# con-bot-j1-0.net
KiCad netlist of a schematic drawn in Altium Designer
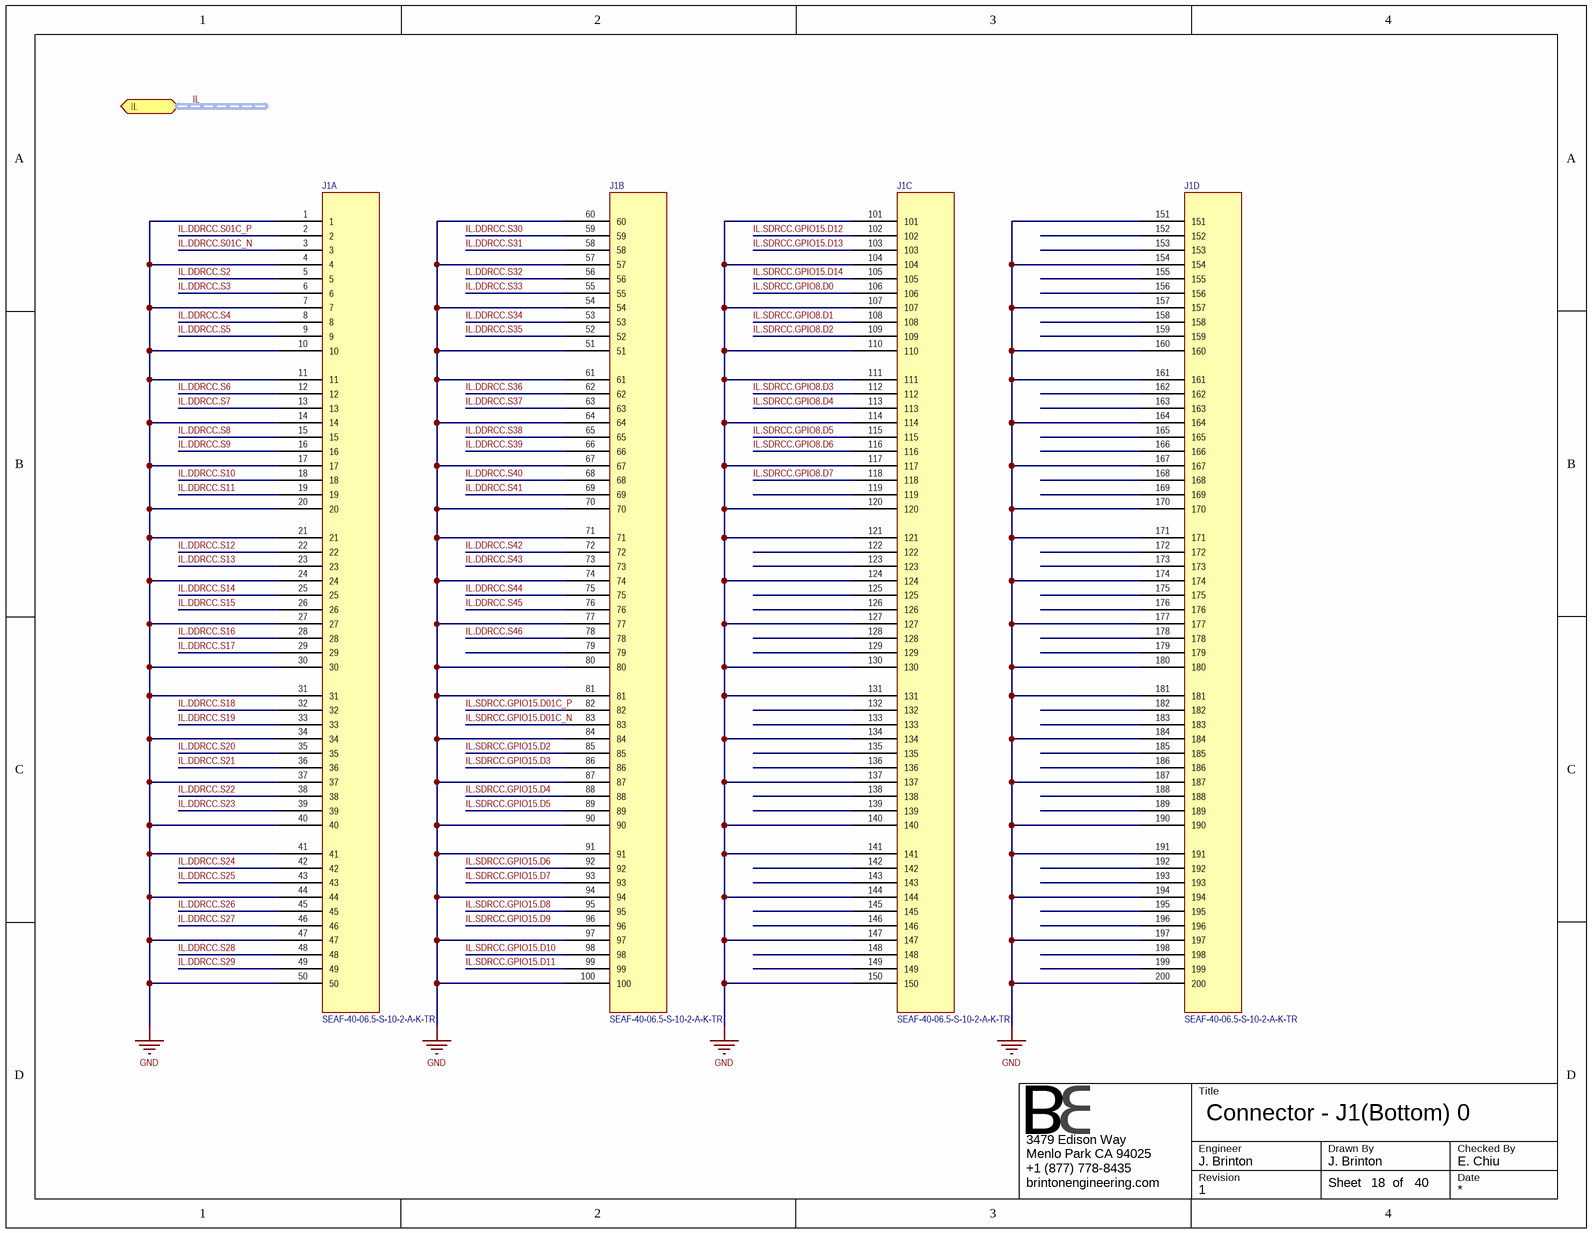
[diagram p0: con-bot-j1-0.SchDoc]

(export (version "E")
  (design (tool "Eeschema 10.0.6"))
  (components
    (comp (ref "J1")
      (value "SEAF-40-06.5-S-10-2-A-K-TR")
      (footprint "samtec:SEAF-40-06.5-S-10-2-A-K-TR")
      (description "Terminal Array Assembly, Surface Mount, 0.050\" Pitch, 400 Pins")
      (fields (field (name "MANUFACTURER") "Samtec"))
      (libsource (lib "samtec") (part "SEAF-40-06.5-S-10-2-A-K-TR"))
    )
  )
  (nets
    (net (code "2") (name "/IL.DDRCC.S01C_N") (class "Default")
      (node (ref "J1") (pin "3") (pinfunction "3_3") (pintype "passive"))
    )
    (net (code "3") (name "/IL.DDRCC.S01C_P") (class "Default")
      (node (ref "J1") (pin "2") (pinfunction "2_2") (pintype "passive"))
    )
    (net (code "4") (name "/IL.DDRCC.S2") (class "Default")
      (node (ref "J1") (pin "5") (pinfunction "5_5") (pintype "passive"))
    )
    (net (code "5") (name "/IL.DDRCC.S3") (class "Default")
      (node (ref "J1") (pin "6") (pinfunction "6_6") (pintype "passive"))
    )
    (net (code "6") (name "/IL.DDRCC.S4") (class "Default")
      (node (ref "J1") (pin "8") (pinfunction "8_8") (pintype "passive"))
    )
    (net (code "7") (name "/IL.DDRCC.S5") (class "Default")
      (node (ref "J1") (pin "9") (pinfunction "9_9") (pintype "passive"))
    )
    (net (code "8") (name "/IL.DDRCC.S6") (class "Default")
      (node (ref "J1") (pin "12") (pinfunction "12_12") (pintype "passive"))
    )
    (net (code "9") (name "/IL.DDRCC.S7") (class "Default")
      (node (ref "J1") (pin "13") (pinfunction "13_13") (pintype "passive"))
    )
    (net (code "10") (name "/IL.DDRCC.S8") (class "Default")
      (node (ref "J1") (pin "15") (pinfunction "15_15") (pintype "passive"))
    )
    (net (code "11") (name "/IL.DDRCC.S9") (class "Default")
      (node (ref "J1") (pin "16") (pinfunction "16_16") (pintype "passive"))
    )
    (net (code "12") (name "/IL.DDRCC.S10") (class "Default")
      (node (ref "J1") (pin "18") (pinfunction "18_18") (pintype "passive"))
    )
    (net (code "13") (name "/IL.DDRCC.S11") (class "Default")
      (node (ref "J1") (pin "19") (pinfunction "19_19") (pintype "passive"))
    )
    (net (code "14") (name "/IL.DDRCC.S12") (class "Default")
      (node (ref "J1") (pin "22") (pinfunction "22_22") (pintype "passive"))
    )
    (net (code "15") (name "/IL.DDRCC.S13") (class "Default")
      (node (ref "J1") (pin "23") (pinfunction "23_23") (pintype "passive"))
    )
    (net (code "16") (name "/IL.DDRCC.S14") (class "Default")
      (node (ref "J1") (pin "25") (pinfunction "25_25") (pintype "passive"))
    )
    (net (code "17") (name "/IL.DDRCC.S15") (class "Default")
      (node (ref "J1") (pin "26") (pinfunction "26_26") (pintype "passive"))
    )
    (net (code "18") (name "/IL.DDRCC.S16") (class "Default")
      (node (ref "J1") (pin "28") (pinfunction "28_28") (pintype "passive"))
    )
    (net (code "19") (name "/IL.DDRCC.S17") (class "Default")
      (node (ref "J1") (pin "29") (pinfunction "29_29") (pintype "passive"))
    )
    (net (code "20") (name "/IL.DDRCC.S18") (class "Default")
      (node (ref "J1") (pin "32") (pinfunction "32_32") (pintype "passive"))
    )
    (net (code "21") (name "/IL.DDRCC.S19") (class "Default")
      (node (ref "J1") (pin "33") (pinfunction "33_33") (pintype "passive"))
    )
    (net (code "22") (name "/IL.DDRCC.S20") (class "Default")
      (node (ref "J1") (pin "35") (pinfunction "35_35") (pintype "passive"))
    )
    (net (code "23") (name "/IL.DDRCC.S21") (class "Default")
      (node (ref "J1") (pin "36") (pinfunction "36_36") (pintype "passive"))
    )
    (net (code "24") (name "/IL.DDRCC.S22") (class "Default")
      (node (ref "J1") (pin "38") (pinfunction "38_38") (pintype "passive"))
    )
    (net (code "25") (name "/IL.DDRCC.S23") (class "Default")
      (node (ref "J1") (pin "39") (pinfunction "39_39") (pintype "passive"))
    )
    (net (code "26") (name "/IL.DDRCC.S24") (class "Default")
      (node (ref "J1") (pin "42") (pinfunction "42_42") (pintype "passive"))
    )
    (net (code "27") (name "/IL.DDRCC.S25") (class "Default")
      (node (ref "J1") (pin "43") (pinfunction "43_43") (pintype "passive"))
    )
    (net (code "28") (name "/IL.DDRCC.S26") (class "Default")
      (node (ref "J1") (pin "45") (pinfunction "45_45") (pintype "passive"))
    )
    (net (code "29") (name "/IL.DDRCC.S27") (class "Default")
      (node (ref "J1") (pin "46") (pinfunction "46_46") (pintype "passive"))
    )
    (net (code "30") (name "/IL.DDRCC.S28") (class "Default")
      (node (ref "J1") (pin "48") (pinfunction "48_48") (pintype "passive"))
    )
    (net (code "31") (name "/IL.DDRCC.S29") (class "Default")
      (node (ref "J1") (pin "49") (pinfunction "49_49") (pintype "passive"))
    )
    (net (code "32") (name "/IL.DDRCC.S30") (class "Default")
      (node (ref "J1") (pin "59") (pinfunction "59_59") (pintype "passive"))
    )
    (net (code "33") (name "/IL.DDRCC.S31") (class "Default")
      (node (ref "J1") (pin "58") (pinfunction "58_58") (pintype "passive"))
    )
    (net (code "34") (name "/IL.DDRCC.S32") (class "Default")
      (node (ref "J1") (pin "56") (pinfunction "56_56") (pintype "passive"))
    )
    (net (code "35") (name "/IL.DDRCC.S33") (class "Default")
      (node (ref "J1") (pin "55") (pinfunction "55_55") (pintype "passive"))
    )
    (net (code "36") (name "/IL.DDRCC.S34") (class "Default")
      (node (ref "J1") (pin "53") (pinfunction "53_53") (pintype "passive"))
    )
    (net (code "37") (name "/IL.DDRCC.S35") (class "Default")
      (node (ref "J1") (pin "52") (pinfunction "52_52") (pintype "passive"))
    )
    (net (code "38") (name "/IL.DDRCC.S36") (class "Default")
      (node (ref "J1") (pin "62") (pinfunction "62_62") (pintype "passive"))
    )
    (net (code "39") (name "/IL.DDRCC.S37") (class "Default")
      (node (ref "J1") (pin "63") (pinfunction "63_63") (pintype "passive"))
    )
    (net (code "40") (name "/IL.DDRCC.S38") (class "Default")
      (node (ref "J1") (pin "65") (pinfunction "65_65") (pintype "passive"))
    )
    (net (code "41") (name "/IL.DDRCC.S39") (class "Default")
      (node (ref "J1") (pin "66") (pinfunction "66_66") (pintype "passive"))
    )
    (net (code "42") (name "/IL.DDRCC.S40") (class "Default")
      (node (ref "J1") (pin "68") (pinfunction "68_68") (pintype "passive"))
    )
    (net (code "43") (name "/IL.DDRCC.S41") (class "Default")
      (node (ref "J1") (pin "69") (pinfunction "69_69") (pintype "passive"))
    )
    (net (code "44") (name "/IL.DDRCC.S42") (class "Default")
      (node (ref "J1") (pin "72") (pinfunction "72_72") (pintype "passive"))
    )
    (net (code "45") (name "/IL.DDRCC.S43") (class "Default")
      (node (ref "J1") (pin "73") (pinfunction "73_73") (pintype "passive"))
    )
    (net (code "46") (name "/IL.DDRCC.S44") (class "Default")
      (node (ref "J1") (pin "75") (pinfunction "75_75") (pintype "passive"))
    )
    (net (code "47") (name "/IL.DDRCC.S45") (class "Default")
      (node (ref "J1") (pin "76") (pinfunction "76_76") (pintype "passive"))
    )
    (net (code "48") (name "/IL.DDRCC.S46") (class "Default")
      (node (ref "J1") (pin "78") (pinfunction "78_78") (pintype "passive"))
    )
    (net (code "49") (name "/IL.SDRCC.GPIO8.D0") (class "Default")
      (node (ref "J1") (pin "106") (pinfunction "106_106") (pintype "passive"))
    )
    (net (code "50") (name "/IL.SDRCC.GPIO8.D1") (class "Default")
      (node (ref "J1") (pin "108") (pinfunction "108_108") (pintype "passive"))
    )
    (net (code "51") (name "/IL.SDRCC.GPIO8.D2") (class "Default")
      (node (ref "J1") (pin "109") (pinfunction "109_109") (pintype "passive"))
    )
    (net (code "52") (name "/IL.SDRCC.GPIO8.D3") (class "Default")
      (node (ref "J1") (pin "112") (pinfunction "112_112") (pintype "passive"))
    )
    (net (code "53") (name "/IL.SDRCC.GPIO8.D4") (class "Default")
      (node (ref "J1") (pin "113") (pinfunction "113_113") (pintype "passive"))
    )
    (net (code "54") (name "/IL.SDRCC.GPIO8.D5") (class "Default")
      (node (ref "J1") (pin "115") (pinfunction "115_115") (pintype "passive"))
    )
    (net (code "55") (name "/IL.SDRCC.GPIO8.D6") (class "Default")
      (node (ref "J1") (pin "116") (pinfunction "116_116") (pintype "passive"))
    )
    (net (code "56") (name "/IL.SDRCC.GPIO8.D7") (class "Default")
      (node (ref "J1") (pin "118") (pinfunction "118_118") (pintype "passive"))
    )
    (net (code "57") (name "/IL.SDRCC.GPIO15.D01C_N") (class "Default")
      (node (ref "J1") (pin "83") (pinfunction "83_83") (pintype "passive"))
    )
    (net (code "58") (name "/IL.SDRCC.GPIO15.D01C_P") (class "Default")
      (node (ref "J1") (pin "82") (pinfunction "82_82") (pintype "passive"))
    )
    (net (code "59") (name "/IL.SDRCC.GPIO15.D2") (class "Default")
      (node (ref "J1") (pin "85") (pinfunction "85_85") (pintype "passive"))
    )
    (net (code "60") (name "/IL.SDRCC.GPIO15.D3") (class "Default")
      (node (ref "J1") (pin "86") (pinfunction "86_86") (pintype "passive"))
    )
    (net (code "61") (name "/IL.SDRCC.GPIO15.D4") (class "Default")
      (node (ref "J1") (pin "88") (pinfunction "88_88") (pintype "passive"))
    )
    (net (code "62") (name "/IL.SDRCC.GPIO15.D5") (class "Default")
      (node (ref "J1") (pin "89") (pinfunction "89_89") (pintype "passive"))
    )
    (net (code "63") (name "/IL.SDRCC.GPIO15.D6") (class "Default")
      (node (ref "J1") (pin "92") (pinfunction "92_92") (pintype "passive"))
    )
    (net (code "64") (name "/IL.SDRCC.GPIO15.D7") (class "Default")
      (node (ref "J1") (pin "93") (pinfunction "93_93") (pintype "passive"))
    )
    (net (code "65") (name "/IL.SDRCC.GPIO15.D8") (class "Default")
      (node (ref "J1") (pin "95") (pinfunction "95_95") (pintype "passive"))
    )
    (net (code "66") (name "/IL.SDRCC.GPIO15.D9") (class "Default")
      (node (ref "J1") (pin "96") (pinfunction "96_96") (pintype "passive"))
    )
    (net (code "67") (name "/IL.SDRCC.GPIO15.D10") (class "Default")
      (node (ref "J1") (pin "98") (pinfunction "98_98") (pintype "passive"))
    )
    (net (code "68") (name "/IL.SDRCC.GPIO15.D11") (class "Default")
      (node (ref "J1") (pin "99") (pinfunction "99_99") (pintype "passive"))
    )
    (net (code "69") (name "/IL.SDRCC.GPIO15.D12") (class "Default")
      (node (ref "J1") (pin "102") (pinfunction "102_102") (pintype "passive"))
    )
    (net (code "70") (name "/IL.SDRCC.GPIO15.D13") (class "Default")
      (node (ref "J1") (pin "103") (pinfunction "103_103") (pintype "passive"))
    )
    (net (code "71") (name "/IL.SDRCC.GPIO15.D14") (class "Default")
      (node (ref "J1") (pin "105") (pinfunction "105_105") (pintype "passive"))
    )
    (net (code "73") (name "GND") (class "Default")
      (node (ref "J1") (pin "1") (pinfunction "1_1") (pintype "passive"))
      (node (ref "J1") (pin "10") (pinfunction "10_10") (pintype "passive"))
      (node (ref "J1") (pin "100") (pinfunction "100_100") (pintype "passive"))
      (node (ref "J1") (pin "101") (pinfunction "101_101") (pintype "passive"))
      (node (ref "J1") (pin "104") (pinfunction "104_104") (pintype "passive"))
      (node (ref "J1") (pin "107") (pinfunction "107_107") (pintype "passive"))
      (node (ref "J1") (pin "11") (pinfunction "11_11") (pintype "passive"))
      (node (ref "J1") (pin "110") (pinfunction "110_110") (pintype "passive"))
      (node (ref "J1") (pin "111") (pinfunction "111_111") (pintype "passive"))
      (node (ref "J1") (pin "114") (pinfunction "114_114") (pintype "passive"))
      (node (ref "J1") (pin "117") (pinfunction "117_117") (pintype "passive"))
      (node (ref "J1") (pin "120") (pinfunction "120_120") (pintype "passive"))
      (node (ref "J1") (pin "121") (pinfunction "121_121") (pintype "passive"))
      (node (ref "J1") (pin "124") (pinfunction "124_124") (pintype "passive"))
      (node (ref "J1") (pin "127") (pinfunction "127_127") (pintype "passive"))
      (node (ref "J1") (pin "130") (pinfunction "130_130") (pintype "passive"))
      (node (ref "J1") (pin "131") (pinfunction "131_131") (pintype "passive"))
      (node (ref "J1") (pin "134") (pinfunction "134_134") (pintype "passive"))
      (node (ref "J1") (pin "137") (pinfunction "137_137") (pintype "passive"))
      (node (ref "J1") (pin "14") (pinfunction "14_14") (pintype "passive"))
      (node (ref "J1") (pin "140") (pinfunction "140_140") (pintype "passive"))
      (node (ref "J1") (pin "141") (pinfunction "141_141") (pintype "passive"))
      (node (ref "J1") (pin "144") (pinfunction "144_144") (pintype "passive"))
      (node (ref "J1") (pin "147") (pinfunction "147_147") (pintype "passive"))
      (node (ref "J1") (pin "150") (pinfunction "150_150") (pintype "passive"))
      (node (ref "J1") (pin "151") (pinfunction "151_151") (pintype "passive"))
      (node (ref "J1") (pin "154") (pinfunction "154_154") (pintype "passive"))
      (node (ref "J1") (pin "157") (pinfunction "157_157") (pintype "passive"))
      (node (ref "J1") (pin "160") (pinfunction "160_160") (pintype "passive"))
      (node (ref "J1") (pin "161") (pinfunction "161_161") (pintype "passive"))
      (node (ref "J1") (pin "164") (pinfunction "164_164") (pintype "passive"))
      (node (ref "J1") (pin "167") (pinfunction "167_167") (pintype "passive"))
      (node (ref "J1") (pin "17") (pinfunction "17_17") (pintype "passive"))
      (node (ref "J1") (pin "170") (pinfunction "170_170") (pintype "passive"))
      (node (ref "J1") (pin "171") (pinfunction "171_171") (pintype "passive"))
      (node (ref "J1") (pin "174") (pinfunction "174_174") (pintype "passive"))
      (node (ref "J1") (pin "177") (pinfunction "177_177") (pintype "passive"))
      (node (ref "J1") (pin "180") (pinfunction "180_180") (pintype "passive"))
      (node (ref "J1") (pin "181") (pinfunction "181_181") (pintype "passive"))
      (node (ref "J1") (pin "184") (pinfunction "184_184") (pintype "passive"))
      (node (ref "J1") (pin "187") (pinfunction "187_187") (pintype "passive"))
      (node (ref "J1") (pin "190") (pinfunction "190_190") (pintype "passive"))
      (node (ref "J1") (pin "191") (pinfunction "191_191") (pintype "passive"))
      (node (ref "J1") (pin "194") (pinfunction "194_194") (pintype "passive"))
      (node (ref "J1") (pin "197") (pinfunction "197_197") (pintype "passive"))
      (node (ref "J1") (pin "20") (pinfunction "20_20") (pintype "passive"))
      (node (ref "J1") (pin "200") (pinfunction "200_200") (pintype "passive"))
      (node (ref "J1") (pin "21") (pinfunction "21_21") (pintype "passive"))
      (node (ref "J1") (pin "24") (pinfunction "24_24") (pintype "passive"))
      (node (ref "J1") (pin "27") (pinfunction "27_27") (pintype "passive"))
      (node (ref "J1") (pin "30") (pinfunction "30_30") (pintype "passive"))
      (node (ref "J1") (pin "31") (pinfunction "31_31") (pintype "passive"))
      (node (ref "J1") (pin "34") (pinfunction "34_34") (pintype "passive"))
      (node (ref "J1") (pin "37") (pinfunction "37_37") (pintype "passive"))
      (node (ref "J1") (pin "4") (pinfunction "4_4") (pintype "passive"))
      (node (ref "J1") (pin "40") (pinfunction "40_40") (pintype "passive"))
      (node (ref "J1") (pin "41") (pinfunction "41_41") (pintype "passive"))
      (node (ref "J1") (pin "44") (pinfunction "44_44") (pintype "passive"))
      (node (ref "J1") (pin "47") (pinfunction "47_47") (pintype "passive"))
      (node (ref "J1") (pin "50") (pinfunction "50_50") (pintype "passive"))
      (node (ref "J1") (pin "51") (pinfunction "51_51") (pintype "passive"))
      (node (ref "J1") (pin "54") (pinfunction "54_54") (pintype "passive"))
      (node (ref "J1") (pin "57") (pinfunction "57_57") (pintype "passive"))
      (node (ref "J1") (pin "60") (pinfunction "60_60") (pintype "passive"))
      (node (ref "J1") (pin "61") (pinfunction "61_61") (pintype "passive"))
      (node (ref "J1") (pin "64") (pinfunction "64_64") (pintype "passive"))
      (node (ref "J1") (pin "67") (pinfunction "67_67") (pintype "passive"))
      (node (ref "J1") (pin "7") (pinfunction "7_7") (pintype "passive"))
      (node (ref "J1") (pin "70") (pinfunction "70_70") (pintype "passive"))
      (node (ref "J1") (pin "71") (pinfunction "71_71") (pintype "passive"))
      (node (ref "J1") (pin "74") (pinfunction "74_74") (pintype "passive"))
      (node (ref "J1") (pin "77") (pinfunction "77_77") (pintype "passive"))
      (node (ref "J1") (pin "80") (pinfunction "80_80") (pintype "passive"))
      (node (ref "J1") (pin "81") (pinfunction "81_81") (pintype "passive"))
      (node (ref "J1") (pin "84") (pinfunction "84_84") (pintype "passive"))
      (node (ref "J1") (pin "87") (pinfunction "87_87") (pintype "passive"))
      (node (ref "J1") (pin "90") (pinfunction "90_90") (pintype "passive"))
      (node (ref "J1") (pin "91") (pinfunction "91_91") (pintype "passive"))
      (node (ref "J1") (pin "94") (pinfunction "94_94") (pintype "passive"))
      (node (ref "J1") (pin "97") (pinfunction "97_97") (pintype "passive"))
    )
    (net (code "74") (name "unconnected-(J1-Pad79)") (class "Default")
      (node (ref "J1") (pin "79") (pinfunction "79_79") (pintype "passive"))
    )
    (net (code "75") (name "unconnected-(J1-Pad119)") (class "Default")
      (node (ref "J1") (pin "119") (pinfunction "119_119") (pintype "passive"))
    )
    (net (code "76") (name "unconnected-(J1-Pad122)") (class "Default")
      (node (ref "J1") (pin "122") (pinfunction "122_122") (pintype "passive"))
    )
    (net (code "77") (name "unconnected-(J1-Pad123)") (class "Default")
      (node (ref "J1") (pin "123") (pinfunction "123_123") (pintype "passive"))
    )
    (net (code "78") (name "unconnected-(J1-Pad125)") (class "Default")
      (node (ref "J1") (pin "125") (pinfunction "125_125") (pintype "passive"))
    )
    (net (code "79") (name "unconnected-(J1-Pad126)") (class "Default")
      (node (ref "J1") (pin "126") (pinfunction "126_126") (pintype "passive"))
    )
    (net (code "80") (name "unconnected-(J1-Pad128)") (class "Default")
      (node (ref "J1") (pin "128") (pinfunction "128_128") (pintype "passive"))
    )
    (net (code "81") (name "unconnected-(J1-Pad129)") (class "Default")
      (node (ref "J1") (pin "129") (pinfunction "129_129") (pintype "passive"))
    )
    (net (code "82") (name "unconnected-(J1-Pad132)") (class "Default")
      (node (ref "J1") (pin "132") (pinfunction "132_132") (pintype "passive"))
    )
    (net (code "83") (name "unconnected-(J1-Pad133)") (class "Default")
      (node (ref "J1") (pin "133") (pinfunction "133_133") (pintype "passive"))
    )
    (net (code "84") (name "unconnected-(J1-Pad135)") (class "Default")
      (node (ref "J1") (pin "135") (pinfunction "135_135") (pintype "passive"))
    )
    (net (code "85") (name "unconnected-(J1-Pad136)") (class "Default")
      (node (ref "J1") (pin "136") (pinfunction "136_136") (pintype "passive"))
    )
    (net (code "86") (name "unconnected-(J1-Pad138)") (class "Default")
      (node (ref "J1") (pin "138") (pinfunction "138_138") (pintype "passive"))
    )
    (net (code "87") (name "unconnected-(J1-Pad139)") (class "Default")
      (node (ref "J1") (pin "139") (pinfunction "139_139") (pintype "passive"))
    )
    (net (code "88") (name "unconnected-(J1-Pad142)") (class "Default")
      (node (ref "J1") (pin "142") (pinfunction "142_142") (pintype "passive"))
    )
    (net (code "89") (name "unconnected-(J1-Pad143)") (class "Default")
      (node (ref "J1") (pin "143") (pinfunction "143_143") (pintype "passive"))
    )
    (net (code "90") (name "unconnected-(J1-Pad145)") (class "Default")
      (node (ref "J1") (pin "145") (pinfunction "145_145") (pintype "passive"))
    )
    (net (code "91") (name "unconnected-(J1-Pad146)") (class "Default")
      (node (ref "J1") (pin "146") (pinfunction "146_146") (pintype "passive"))
    )
    (net (code "92") (name "unconnected-(J1-Pad148)") (class "Default")
      (node (ref "J1") (pin "148") (pinfunction "148_148") (pintype "passive"))
    )
    (net (code "93") (name "unconnected-(J1-Pad149)") (class "Default")
      (node (ref "J1") (pin "149") (pinfunction "149_149") (pintype "passive"))
    )
    (net (code "94") (name "unconnected-(J1-Pad152)") (class "Default")
      (node (ref "J1") (pin "152") (pinfunction "152_152") (pintype "passive"))
    )
    (net (code "95") (name "unconnected-(J1-Pad153)") (class "Default")
      (node (ref "J1") (pin "153") (pinfunction "153_153") (pintype "passive"))
    )
    (net (code "96") (name "unconnected-(J1-Pad155)") (class "Default")
      (node (ref "J1") (pin "155") (pinfunction "155_155") (pintype "passive"))
    )
    (net (code "97") (name "unconnected-(J1-Pad156)") (class "Default")
      (node (ref "J1") (pin "156") (pinfunction "156_156") (pintype "passive"))
    )
    (net (code "98") (name "unconnected-(J1-Pad158)") (class "Default")
      (node (ref "J1") (pin "158") (pinfunction "158_158") (pintype "passive"))
    )
    (net (code "99") (name "unconnected-(J1-Pad159)") (class "Default")
      (node (ref "J1") (pin "159") (pinfunction "159_159") (pintype "passive"))
    )
    (net (code "100") (name "unconnected-(J1-Pad162)") (class "Default")
      (node (ref "J1") (pin "162") (pinfunction "162_162") (pintype "passive"))
    )
    (net (code "101") (name "unconnected-(J1-Pad163)") (class "Default")
      (node (ref "J1") (pin "163") (pinfunction "163_163") (pintype "passive"))
    )
    (net (code "102") (name "unconnected-(J1-Pad165)") (class "Default")
      (node (ref "J1") (pin "165") (pinfunction "165_165") (pintype "passive"))
    )
    (net (code "103") (name "unconnected-(J1-Pad166)") (class "Default")
      (node (ref "J1") (pin "166") (pinfunction "166_166") (pintype "passive"))
    )
    (net (code "104") (name "unconnected-(J1-Pad168)") (class "Default")
      (node (ref "J1") (pin "168") (pinfunction "168_168") (pintype "passive"))
    )
    (net (code "105") (name "unconnected-(J1-Pad169)") (class "Default")
      (node (ref "J1") (pin "169") (pinfunction "169_169") (pintype "passive"))
    )
    (net (code "106") (name "unconnected-(J1-Pad172)") (class "Default")
      (node (ref "J1") (pin "172") (pinfunction "172_172") (pintype "passive"))
    )
    (net (code "107") (name "unconnected-(J1-Pad173)") (class "Default")
      (node (ref "J1") (pin "173") (pinfunction "173_173") (pintype "passive"))
    )
    (net (code "108") (name "unconnected-(J1-Pad175)") (class "Default")
      (node (ref "J1") (pin "175") (pinfunction "175_175") (pintype "passive"))
    )
    (net (code "109") (name "unconnected-(J1-Pad176)") (class "Default")
      (node (ref "J1") (pin "176") (pinfunction "176_176") (pintype "passive"))
    )
    (net (code "110") (name "unconnected-(J1-Pad178)") (class "Default")
      (node (ref "J1") (pin "178") (pinfunction "178_178") (pintype "passive"))
    )
    (net (code "111") (name "unconnected-(J1-Pad179)") (class "Default")
      (node (ref "J1") (pin "179") (pinfunction "179_179") (pintype "passive"))
    )
    (net (code "112") (name "unconnected-(J1-Pad182)") (class "Default")
      (node (ref "J1") (pin "182") (pinfunction "182_182") (pintype "passive"))
    )
    (net (code "113") (name "unconnected-(J1-Pad183)") (class "Default")
      (node (ref "J1") (pin "183") (pinfunction "183_183") (pintype "passive"))
    )
    (net (code "114") (name "unconnected-(J1-Pad185)") (class "Default")
      (node (ref "J1") (pin "185") (pinfunction "185_185") (pintype "passive"))
    )
    (net (code "115") (name "unconnected-(J1-Pad186)") (class "Default")
      (node (ref "J1") (pin "186") (pinfunction "186_186") (pintype "passive"))
    )
    (net (code "116") (name "unconnected-(J1-Pad188)") (class "Default")
      (node (ref "J1") (pin "188") (pinfunction "188_188") (pintype "passive"))
    )
    (net (code "117") (name "unconnected-(J1-Pad189)") (class "Default")
      (node (ref "J1") (pin "189") (pinfunction "189_189") (pintype "passive"))
    )
    (net (code "118") (name "unconnected-(J1-Pad192)") (class "Default")
      (node (ref "J1") (pin "192") (pinfunction "192_192") (pintype "passive"))
    )
    (net (code "119") (name "unconnected-(J1-Pad193)") (class "Default")
      (node (ref "J1") (pin "193") (pinfunction "193_193") (pintype "passive"))
    )
    (net (code "120") (name "unconnected-(J1-Pad195)") (class "Default")
      (node (ref "J1") (pin "195") (pinfunction "195_195") (pintype "passive"))
    )
    (net (code "121") (name "unconnected-(J1-Pad196)") (class "Default")
      (node (ref "J1") (pin "196") (pinfunction "196_196") (pintype "passive"))
    )
    (net (code "122") (name "unconnected-(J1-Pad198)") (class "Default")
      (node (ref "J1") (pin "198") (pinfunction "198_198") (pintype "passive"))
    )
    (net (code "123") (name "unconnected-(J1-Pad199)") (class "Default")
      (node (ref "J1") (pin "199") (pinfunction "199_199") (pintype "passive"))
    )
  )
)
